# mb_01-5.net
KiCad netlist of a schematic drawn in EAGLE
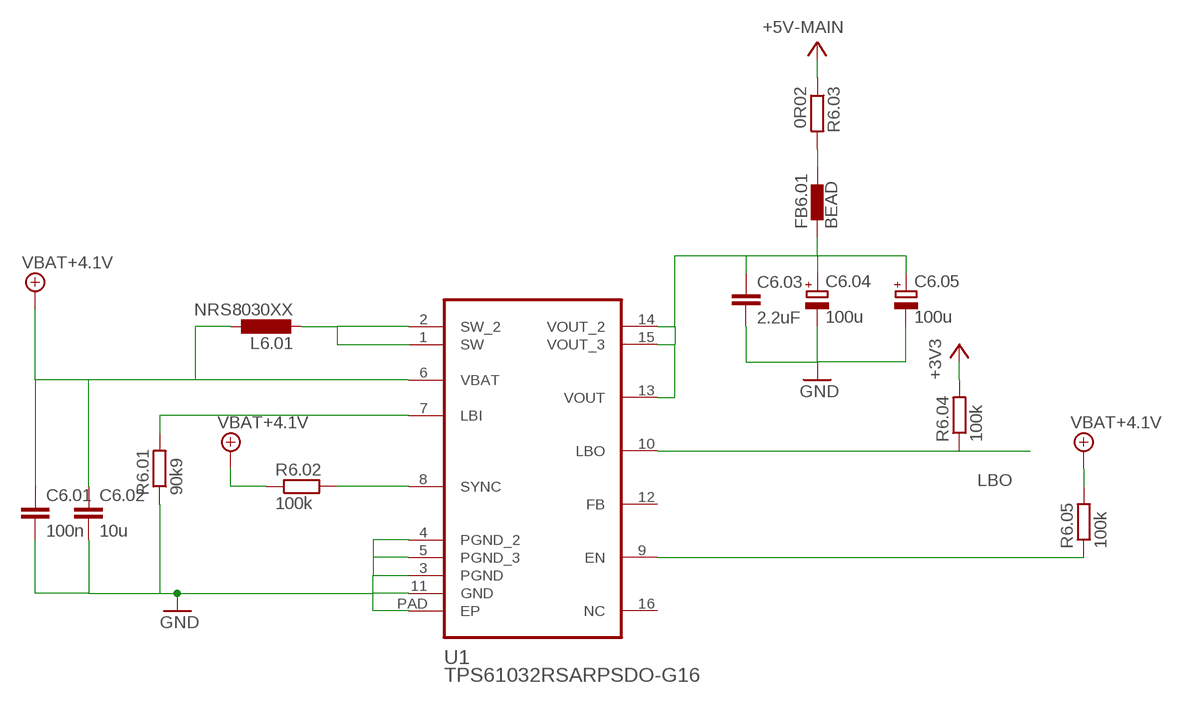
[diagram p0: schematic, sheet 1]

(export (version "E")
  (design (tool "Eeschema 10.0.6"))
  (components
    (comp (ref "C6.01")
      (value "100n")
      (footprint "eagle-import:C0402")
      (libsource (lib "eagle-import") (part "C-EUC0402"))
    )
    (comp (ref "C6.02")
      (value "10u")
      (footprint "eagle-import:C0603")
      (libsource (lib "eagle-import") (part "C-EUC0603"))
    )
    (comp (ref "C6.03")
      (value "2.2uF")
      (footprint "eagle-import:C0603")
      (libsource (lib "eagle-import") (part "C-EUC0603"))
    )
    (comp (ref "C6.04")
      (value "100u")
      (footprint "eagle-import:C-2312")
      (libsource (lib "eagle-import") (part "CPOL-29172312"))
    )
    (comp (ref "C6.05")
      (value "100u")
      (footprint "eagle-import:C-2312")
      (libsource (lib "eagle-import") (part "CPOL-29172312"))
    )
    (comp (ref "FB6.01")
      (value "BEAD")
      (footprint "eagle-import:0402")
      (libsource (lib "eagle-import") (part "BLM15HB121SN1"))
    )
    (comp (ref "L6.01")
      (value "NRS8030XX")
      (footprint "eagle-import:TAIYO-YUDEN.NRS8030T4R7MJGJ")
      (libsource (lib "eagle-import") (part "NRS8030XX"))
    )
    (comp (ref "R6.01")
      (value "90k9")
      (footprint "eagle-import:R0402")
      (libsource (lib "eagle-import") (part "R-EU_R0402"))
    )
    (comp (ref "R6.02")
      (value "100k")
      (footprint "eagle-import:R0402")
      (libsource (lib "eagle-import") (part "R-EU_R0402"))
    )
    (comp (ref "R6.03")
      (value "0R02")
      (footprint "eagle-import:R0805")
      (libsource (lib "eagle-import") (part "R-EU_R0805"))
    )
    (comp (ref "R6.04")
      (value "100k")
      (footprint "eagle-import:R0402")
      (libsource (lib "eagle-import") (part "R-EU_R0402"))
    )
    (comp (ref "R6.05")
      (value "100k")
      (footprint "eagle-import:R0402")
      (libsource (lib "eagle-import") (part "R-EU_R0402"))
    )
    (comp (ref "U1")
      (value "TPS61032RSARPSDO-G16")
      (footprint "eagle-import:R-PDSO-G16")
      (libsource (lib "eagle-import") (part "TPS61032RSARPSDO-G16"))
    )
  )
  (nets
    (net (code "1") (name "+3V3") (class "Default")
      (node (ref "R6.04") (pin "2") (pinfunction "2_2") (pintype "passive"))
    )
    (net (code "2") (name "+5V-MAIN") (class "Default")
      (node (ref "R6.03") (pin "1") (pinfunction "1_1") (pintype "passive"))
    )
    (net (code "3") (name "/LBO") (class "Default")
      (node (ref "R6.04") (pin "1") (pinfunction "1_1") (pintype "passive"))
      (node (ref "U1") (pin "10") (pinfunction "LBO_10") (pintype "output"))
    )
    (net (code "4") (name "GND") (class "Default")
      (node (ref "C6.01") (pin "2") (pinfunction "2_2") (pintype "passive"))
      (node (ref "C6.02") (pin "2") (pinfunction "2_2") (pintype "passive"))
      (node (ref "C6.03") (pin "2") (pinfunction "2_2") (pintype "passive"))
      (node (ref "C6.04") (pin "N") (pinfunction "-_N") (pintype "passive"))
      (node (ref "C6.05") (pin "N") (pinfunction "-_N") (pintype "passive"))
      (node (ref "R6.01") (pin "1") (pinfunction "1_1") (pintype "passive"))
      (node (ref "U1") (pin "11") (pinfunction "GND_11") (pintype "passive"))
      (node (ref "U1") (pin "3") (pinfunction "PGND_3") (pintype "passive"))
      (node (ref "U1") (pin "4") (pinfunction "PGND_2_4") (pintype "passive"))
      (node (ref "U1") (pin "5") (pinfunction "PGND_3_5") (pintype "passive"))
      (node (ref "U1") (pin "PAD") (pinfunction "EP_PAD") (pintype "passive"))
    )
    (net (code "5") (name "Net-(C6.04-+)") (class "Default")
      (node (ref "C6.03") (pin "1") (pinfunction "1_1") (pintype "passive"))
      (node (ref "C6.04") (pin "P") (pinfunction "+_P") (pintype "passive"))
      (node (ref "C6.05") (pin "P") (pinfunction "+_P") (pintype "passive"))
      (node (ref "FB6.01") (pin "1") (pinfunction "1_1") (pintype "passive"))
      (node (ref "U1") (pin "13") (pinfunction "VOUT_13") (pintype "output"))
      (node (ref "U1") (pin "14") (pinfunction "VOUT_2_14") (pintype "output"))
      (node (ref "U1") (pin "15") (pinfunction "VOUT_3_15") (pintype "output"))
    )
    (net (code "6") (name "Net-(FB6.01-Pad2)") (class "Default")
      (node (ref "FB6.01") (pin "2") (pinfunction "2_2") (pintype "passive"))
      (node (ref "R6.03") (pin "2") (pinfunction "2_2") (pintype "passive"))
    )
    (net (code "7") (name "Net-(U1-EN)") (class "Default")
      (node (ref "R6.05") (pin "1") (pinfunction "1_1") (pintype "passive"))
      (node (ref "U1") (pin "9") (pinfunction "EN_9") (pintype "input"))
    )
    (net (code "8") (name "Net-(U1-LBI)") (class "Default")
      (node (ref "R6.01") (pin "2") (pinfunction "2_2") (pintype "passive"))
      (node (ref "U1") (pin "7") (pinfunction "LBI_7") (pintype "input"))
    )
    (net (code "9") (name "Net-(U1-SW)") (class "Default")
      (node (ref "L6.01") (pin "2") (pinfunction "2_2") (pintype "passive"))
      (node (ref "U1") (pin "1") (pinfunction "SW_1") (pintype "input"))
      (node (ref "U1") (pin "2") (pinfunction "SW_2_2") (pintype "input"))
    )
    (net (code "10") (name "Net-(U1-SYNC)") (class "Default")
      (node (ref "R6.02") (pin "2") (pinfunction "2_2") (pintype "passive"))
      (node (ref "U1") (pin "8") (pinfunction "SYNC_8") (pintype "input"))
    )
    (net (code "11") (name "VBAT+4.1V") (class "Default")
      (node (ref "C6.01") (pin "1") (pinfunction "1_1") (pintype "passive"))
      (node (ref "C6.02") (pin "1") (pinfunction "1_1") (pintype "passive"))
      (node (ref "L6.01") (pin "1") (pinfunction "1_1") (pintype "passive"))
      (node (ref "R6.02") (pin "1") (pinfunction "1_1") (pintype "passive"))
      (node (ref "R6.05") (pin "2") (pinfunction "2_2") (pintype "passive"))
      (node (ref "U1") (pin "6") (pinfunction "VBAT_6") (pintype "input"))
    )
    (net (code "12") (name "unconnected-(U1-FB-Pad12)") (class "Default")
      (node (ref "U1") (pin "12") (pinfunction "FB_12") (pintype "input"))
    )
    (net (code "13") (name "unconnected-(U1-NC-Pad16)") (class "Default")
      (node (ref "U1") (pin "16") (pinfunction "NC_16") (pintype "no_connect"))
    )
  )
)
